# SCH_UsbHub_2024-08-12.net
KiCad netlist of a schematic drawn in EasyEDA
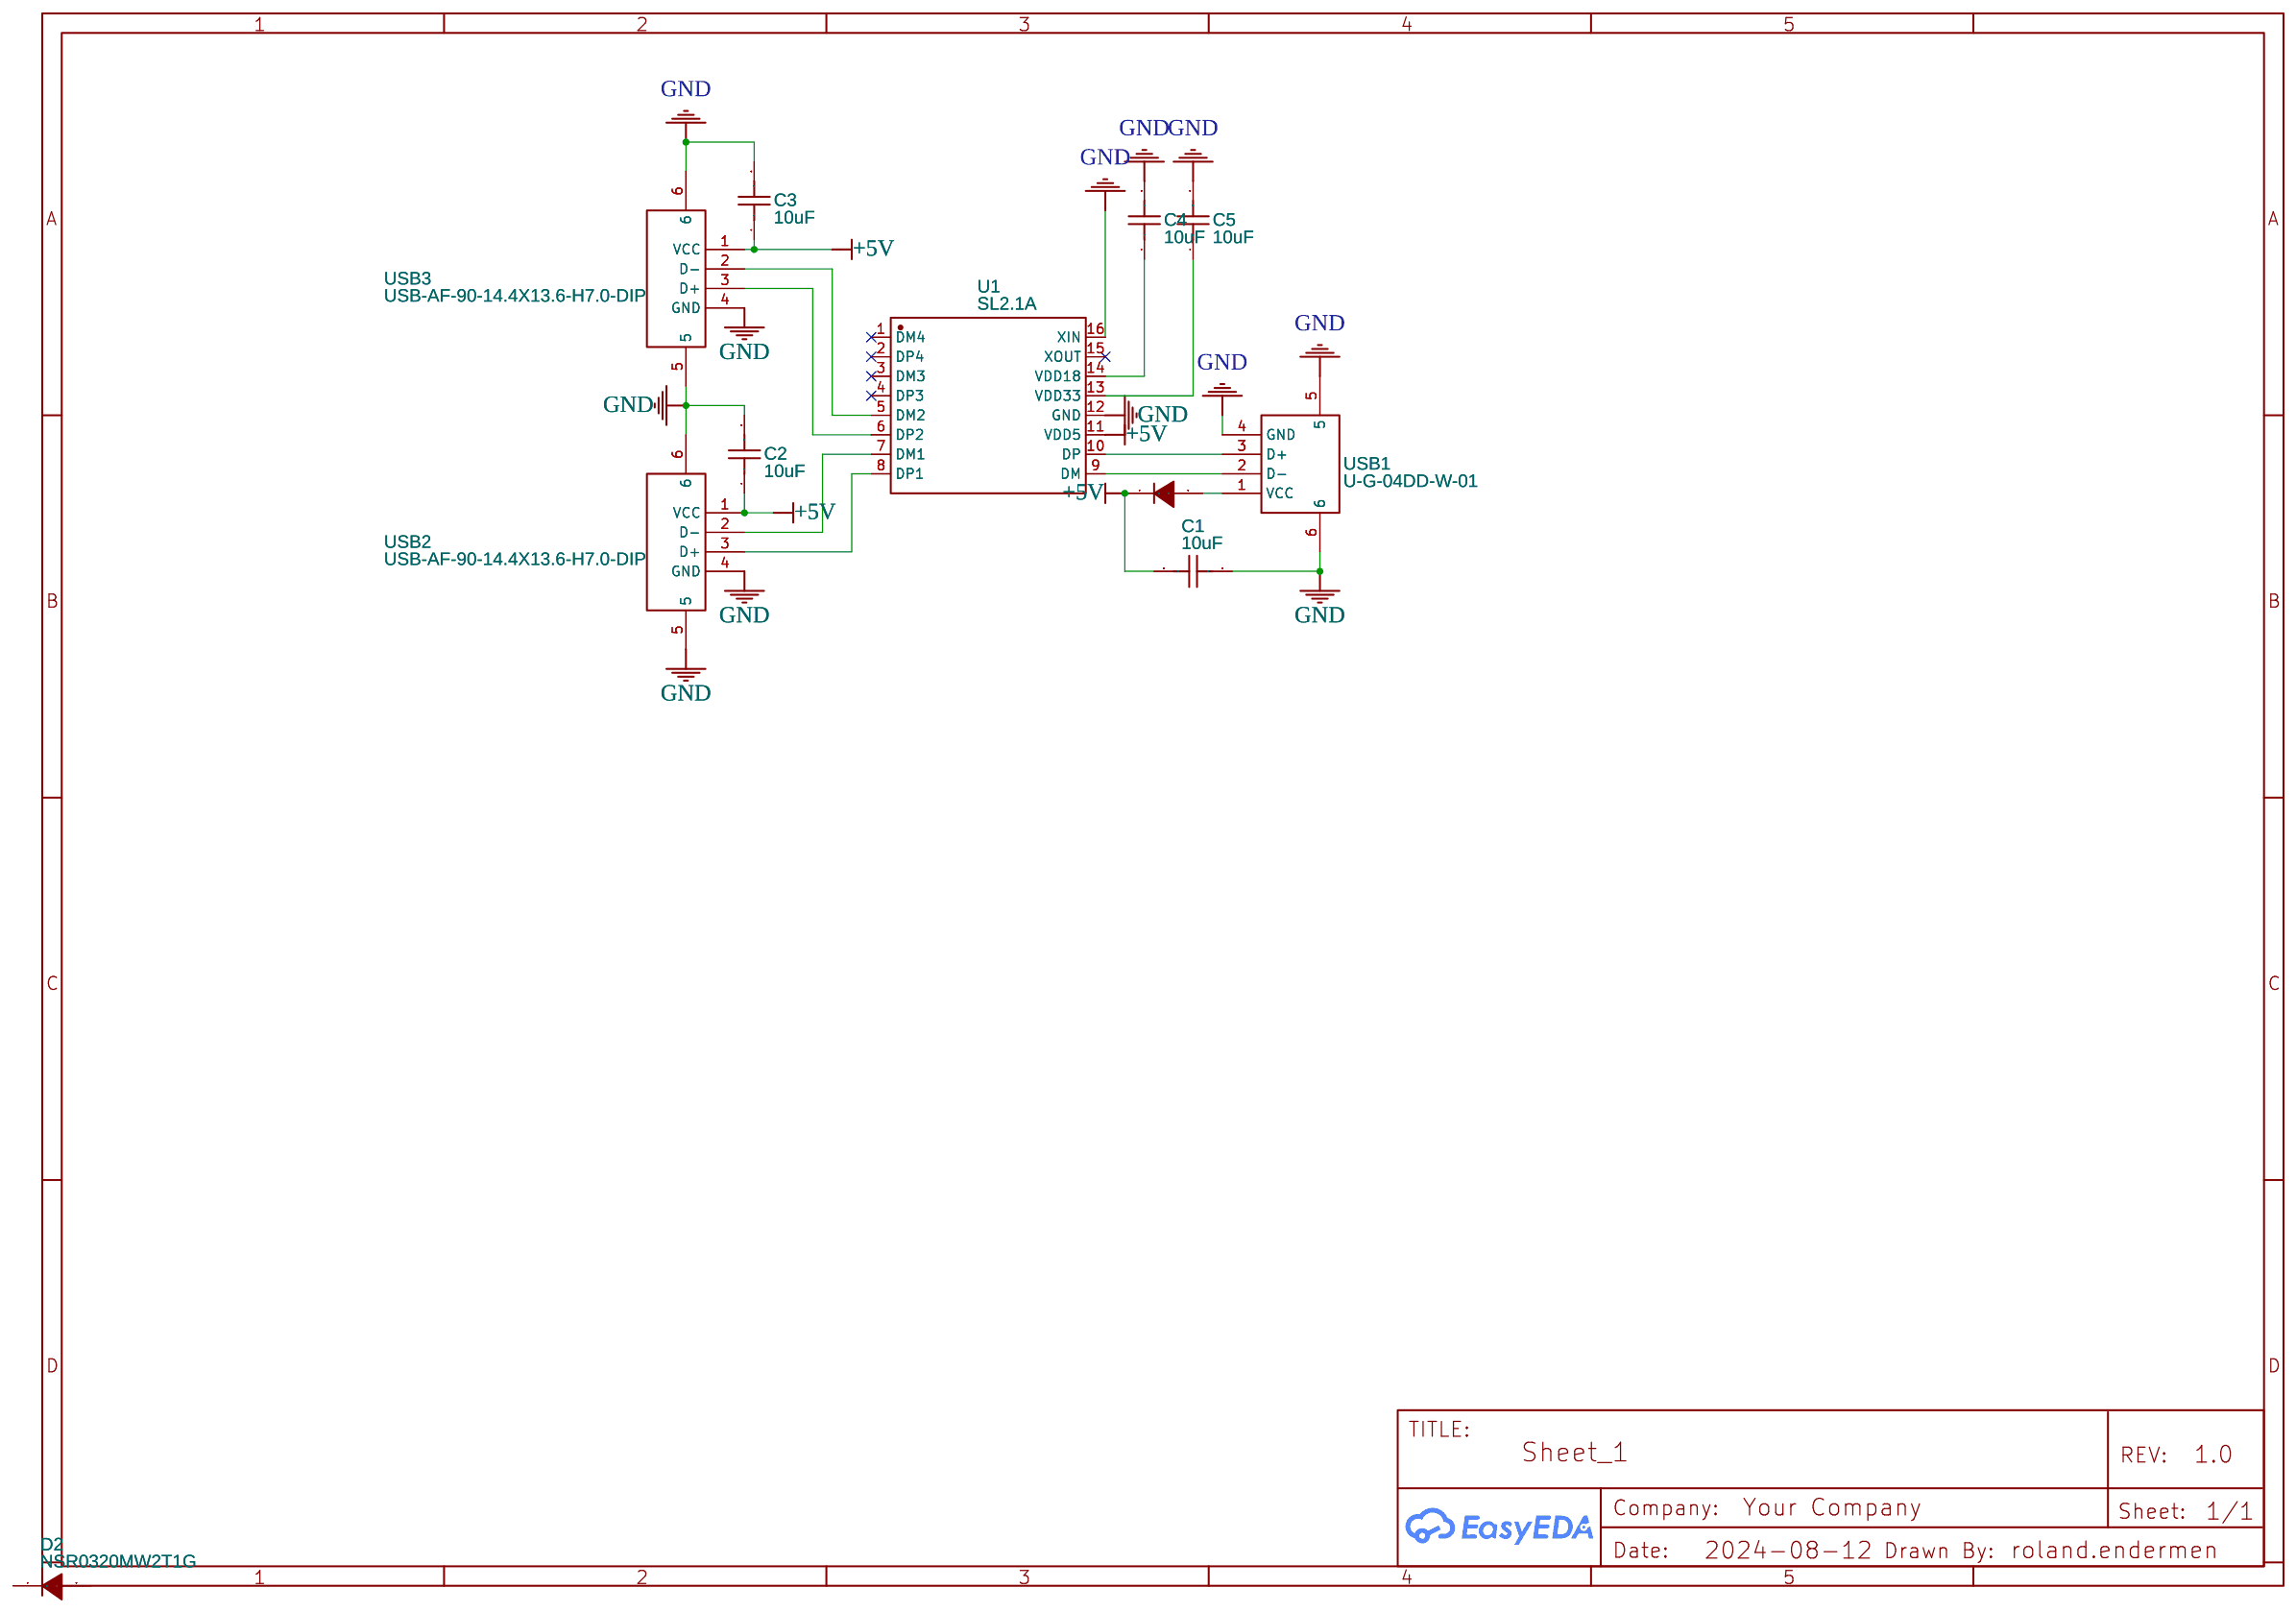
[diagram p0: schematic sheet]

(export (version "E")
  (design (tool "Eeschema 10.0.6"))
  (components
    (comp (ref "C1")
      (value "10uF")
      (fields
        (field (name "Manufacturer Part") "CL10A106KP8NNNC")
        (field (name "Manufacturer") "SAMSUNG(三星)")
      )
      (libsource (lib "") (part "CL10A106KP8NNNC_1"))
    )
    (comp (ref "C2")
      (value "10uF")
      (fields
        (field (name "Manufacturer Part") "CL10A106KP8NNNC")
        (field (name "Manufacturer") "SAMSUNG(三星)")
      )
      (libsource (lib "") (part "CL10A106KP8NNNC"))
    )
    (comp (ref "C3")
      (value "10uF")
      (fields
        (field (name "Manufacturer Part") "CL10A106KP8NNNC")
        (field (name "Manufacturer") "SAMSUNG(三星)")
      )
      (libsource (lib "") (part "CL10A106KP8NNNC"))
    )
    (comp (ref "C4")
      (value "10uF")
      (fields
        (field (name "Manufacturer Part") "CL10A106KP8NNNC")
        (field (name "Manufacturer") "SAMSUNG(三星)")
      )
      (libsource (lib "") (part "CL10A106KP8NNNC"))
    )
    (comp (ref "C5")
      (value "10uF")
      (fields
        (field (name "Manufacturer Part") "CL10A106KP8NNNC")
        (field (name "Manufacturer") "SAMSUNG(三星)")
      )
      (libsource (lib "") (part "CL10A106KP8NNNC"))
    )
    (comp (ref "D1")
      (value "NSR0320MW2T1G")
      (fields (field (name "Manufacturer") "onsemi(安森美)"))
      (libsource (lib "") (part "NSR0320MW2T1G"))
    )
    (comp (ref "D2")
      (value "NSR0320MW2T1G")
      (fields (field (name "Manufacturer") "onsemi(安森美)"))
      (libsource (lib "") (part "NSR0320MW2T1G"))
    )
    (comp (ref "U1")
      (value "SL2.1A")
      (fields (field (name "Manufacturer") "CoreChips(和芯润德)"))
      (libsource (lib "") (part "SL2.1A"))
    )
    (comp (ref "USB1")
      (value "U-G-04DD-W-01")
      (fields (field (name "Manufacturer Part") "U-G-O4DD-W-1") (field (name "Manufacturer") "韩国韩荣"))
      (libsource (lib "") (part "U-G-04DD-W-01"))
    )
    (comp (ref "USB2")
      (value "USB-AF-90-14.4X13.6-H7.0-DIP")
      (fields (field (name "Manufacturer Part") "903-131A1011D10100") (field (name "Manufacturer") "精拓金"))
      (libsource (lib "") (part "USB-AF-90-14.4X13.6-H7.0-DIP"))
    )
    (comp (ref "USB3")
      (value "USB-AF-90-14.4X13.6-H7.0-DIP")
      (fields (field (name "Manufacturer Part") "903-131A1011D10100") (field (name "Manufacturer") "精拓金"))
      (libsource (lib "") (part "USB-AF-90-14.4X13.6-H7.0-DIP"))
    )
  )
  (nets
    (net (code "1") (name "+5V") (class "Default")
      (node (ref "C1") (pin "1") (pinfunction "1_1") (pintype "unspecified"))
      (node (ref "C2") (pin "1") (pinfunction "1_1") (pintype "unspecified"))
      (node (ref "C3") (pin "1") (pinfunction "1_1") (pintype "unspecified"))
      (node (ref "D1") (pin "1") (pinfunction "C_1") (pintype "unspecified"))
      (node (ref "U1") (pin "11") (pinfunction "VDD5_11") (pintype "unspecified"))
      (node (ref "USB2") (pin "1") (pinfunction "VCC_1") (pintype "unspecified"))
      (node (ref "USB3") (pin "1") (pinfunction "VCC_1") (pintype "unspecified"))
    )
    (net (code "2") (name "GND") (class "Default")
      (node (ref "C1") (pin "2") (pinfunction "2_2") (pintype "unspecified"))
      (node (ref "C2") (pin "2") (pinfunction "2_2") (pintype "unspecified"))
      (node (ref "C3") (pin "2") (pinfunction "2_2") (pintype "unspecified"))
      (node (ref "C4") (pin "2") (pinfunction "2_2") (pintype "unspecified"))
      (node (ref "C5") (pin "2") (pinfunction "2_2") (pintype "unspecified"))
      (node (ref "U1") (pin "12") (pinfunction "GND_12") (pintype "unspecified"))
      (node (ref "U1") (pin "16") (pinfunction "XIN_16") (pintype "unspecified"))
      (node (ref "USB1") (pin "4") (pinfunction "GND_4") (pintype "unspecified"))
      (node (ref "USB1") (pin "5") (pinfunction "5_5") (pintype "unspecified"))
      (node (ref "USB1") (pin "6") (pinfunction "6_6") (pintype "unspecified"))
      (node (ref "USB2") (pin "4") (pinfunction "GND_4") (pintype "unspecified"))
      (node (ref "USB2") (pin "5") (pinfunction "5_5") (pintype "unspecified"))
      (node (ref "USB2") (pin "6") (pinfunction "6_6") (pintype "unspecified"))
      (node (ref "USB3") (pin "4") (pinfunction "GND_4") (pintype "unspecified"))
      (node (ref "USB3") (pin "5") (pinfunction "5_5") (pintype "unspecified"))
      (node (ref "USB3") (pin "6") (pinfunction "6_6") (pintype "unspecified"))
    )
    (net (code "3") (name "Net-(D1-A)") (class "Default")
      (node (ref "D1") (pin "2") (pinfunction "A_2") (pintype "unspecified"))
      (node (ref "USB1") (pin "1") (pinfunction "VCC_1") (pintype "unspecified"))
    )
    (net (code "4") (name "Net-(U1-DM)") (class "Default")
      (node (ref "U1") (pin "9") (pinfunction "DM_9") (pintype "unspecified"))
      (node (ref "USB1") (pin "2") (pinfunction "D-_2") (pintype "unspecified"))
    )
    (net (code "5") (name "Net-(U1-DM1)") (class "Default")
      (node (ref "U1") (pin "7") (pinfunction "DM1_7") (pintype "unspecified"))
      (node (ref "USB2") (pin "2") (pinfunction "D-_2") (pintype "unspecified"))
    )
    (net (code "6") (name "Net-(U1-DM2)") (class "Default")
      (node (ref "U1") (pin "5") (pinfunction "DM2_5") (pintype "unspecified"))
      (node (ref "USB3") (pin "2") (pinfunction "D-_2") (pintype "unspecified"))
    )
    (net (code "7") (name "Net-(U1-DP)") (class "Default")
      (node (ref "U1") (pin "10") (pinfunction "DP_10") (pintype "unspecified"))
      (node (ref "USB1") (pin "3") (pinfunction "D+_3") (pintype "unspecified"))
    )
    (net (code "8") (name "Net-(U1-DP1)") (class "Default")
      (node (ref "U1") (pin "8") (pinfunction "DP1_8") (pintype "unspecified"))
      (node (ref "USB2") (pin "3") (pinfunction "D+_3") (pintype "unspecified"))
    )
    (net (code "9") (name "Net-(U1-DP2)") (class "Default")
      (node (ref "U1") (pin "6") (pinfunction "DP2_6") (pintype "unspecified"))
      (node (ref "USB3") (pin "3") (pinfunction "D+_3") (pintype "unspecified"))
    )
    (net (code "10") (name "Net-(U1-VDD18)") (class "Default")
      (node (ref "C4") (pin "1") (pinfunction "1_1") (pintype "unspecified"))
      (node (ref "U1") (pin "14") (pinfunction "VDD18_14") (pintype "unspecified"))
    )
    (net (code "11") (name "Net-(U1-VDD33)") (class "Default")
      (node (ref "C5") (pin "1") (pinfunction "1_1") (pintype "unspecified"))
      (node (ref "U1") (pin "13") (pinfunction "VDD33_13") (pintype "unspecified"))
    )
    (net (code "12") (name "unconnected-(D2-A-Pad2)") (class "Default")
      (node (ref "D2") (pin "2") (pinfunction "A_2") (pintype "unspecified"))
    )
    (net (code "13") (name "unconnected-(D2-C-Pad1)") (class "Default")
      (node (ref "D2") (pin "1") (pinfunction "C_1") (pintype "unspecified"))
    )
    (net (code "14") (name "unconnected-(U1-DM3-Pad3)") (class "Default")
      (node (ref "U1") (pin "3") (pinfunction "DM3_3") (pintype "unspecified+no_connect"))
    )
    (net (code "15") (name "unconnected-(U1-DM4-Pad1)") (class "Default")
      (node (ref "U1") (pin "1") (pinfunction "DM4_1") (pintype "unspecified+no_connect"))
    )
    (net (code "16") (name "unconnected-(U1-DP3-Pad4)") (class "Default")
      (node (ref "U1") (pin "4") (pinfunction "DP3_4") (pintype "unspecified+no_connect"))
    )
    (net (code "17") (name "unconnected-(U1-DP4-Pad2)") (class "Default")
      (node (ref "U1") (pin "2") (pinfunction "DP4_2") (pintype "unspecified+no_connect"))
    )
    (net (code "18") (name "unconnected-(U1-XOUT-Pad15)") (class "Default")
      (node (ref "U1") (pin "15") (pinfunction "XOUT_15") (pintype "unspecified+no_connect"))
    )
  )
)
